# Placa_Final_Embebidos_Displays.net
KiCad netlist of a schematic drawn in Altium Designer
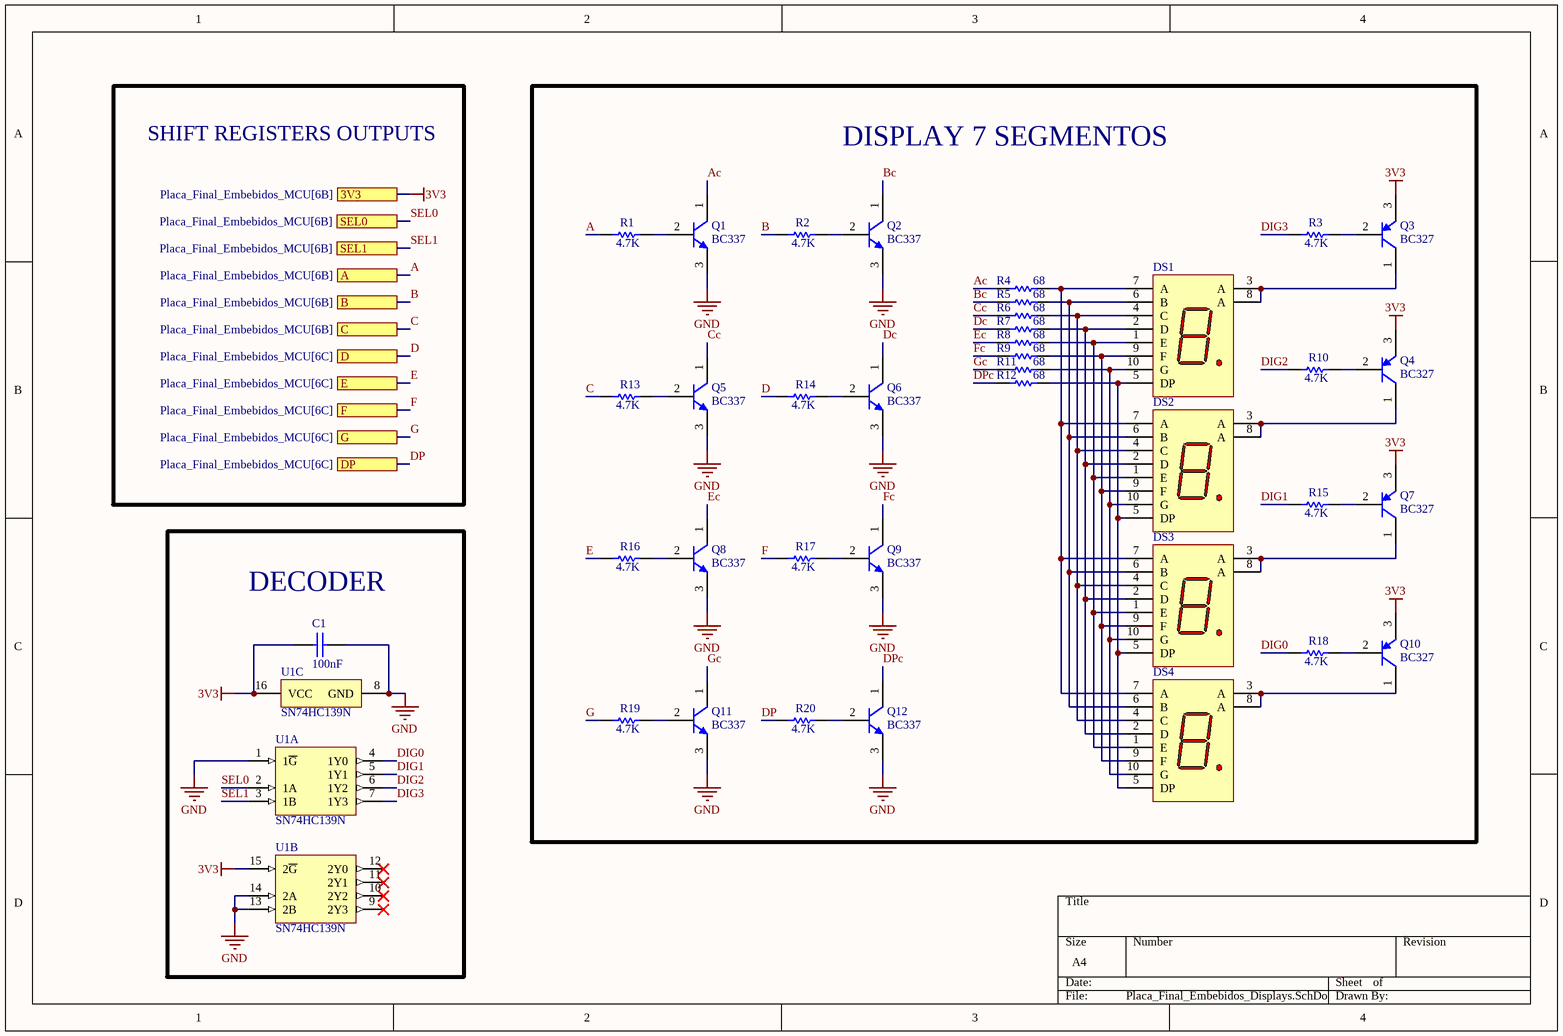
[diagram p0: Placa_Final_Embebidos_Displays.SchDoc]

(export (version "E")
  (design (tool "Eeschema 10.0.6"))
  (components
    (comp (ref "C1") (value "100nF") (footprint "CAP200") (libsource (lib "LIB PIO IX") (part "CAP")))
    (comp (ref "DS1")
      (value "~")
      (footprint "WL-T7DS_L17.5W12.4H7")
      (description "7-Seg Display, Comm Anode, Super Red Rohs Compliant: Yes")
      (libsource (lib "Altium Content Vault") (part "7 Segments_Red_CA_type 1"))
    )
    (comp (ref "DS2")
      (value "~")
      (footprint "WL-T7DS_L17.5W12.4H7")
      (description "7-Seg Display, Comm Anode, Super Red Rohs Compliant: Yes")
      (libsource (lib "Altium Content Vault") (part "7 Segments_Red_CA_type 1"))
    )
    (comp (ref "DS3")
      (value "~")
      (footprint "WL-T7DS_L17.5W12.4H7")
      (description "7-Seg Display, Comm Anode, Super Red Rohs Compliant: Yes")
      (libsource (lib "Altium Content Vault") (part "7 Segments_Red_CA_type 1"))
    )
    (comp (ref "DS4")
      (value "~")
      (footprint "WL-T7DS_L17.5W12.4H7")
      (description "7-Seg Display, Comm Anode, Super Red Rohs Compliant: Yes")
      (libsource (lib "Altium Content Vault") (part "7 Segments_Red_CA_type 1"))
    )
    (comp (ref "Q1")
      (value "BC337")
      (footprint "ONSC-TO-92-3-29-11_AM_BL")
      (description "Amplifier Transistor, NPN Silicon, 3-Pin TO-92, Pb-Free, Ammo Box")
      (fields (field (name "PARTNUMBER") "BC337-40ZL1G") (field (name "MANUFACTURER") "On Semiconductor"))
      (libsource (lib "Altium Content Vault") (part "ONSC-NPN-C1B2E3-3"))
    )
    (comp (ref "Q2")
      (value "BC337")
      (footprint "ONSC-TO-92-3-29-11_AM_BL")
      (description "Amplifier Transistor, NPN Silicon, 3-Pin TO-92, Pb-Free, Ammo Box")
      (fields (field (name "PARTNUMBER") "BC337-40ZL1G") (field (name "MANUFACTURER") "On Semiconductor"))
      (libsource (lib "Altium Content Vault") (part "ONSC-NPN-C1B2E3-3"))
    )
    (comp (ref "Q3")
      (value "BC327")
      (footprint "ONSC-TO-92-3-29-11_AM_BL")
      (description "Amplifier Transistor, PNP Silicon, 3-Pin TO-92, Pb-Free, Ammo Box")
      (fields (field (name "MANUFACTURER") "On Semiconductor") (field (name "PARTNUMBER") "BC327-25ZL1G"))
      (libsource (lib "Altium Content Vault") (part "ONSC-PNP-C1B2E3-3"))
    )
    (comp (ref "Q4")
      (value "BC327")
      (footprint "ONSC-TO-92-3-29-11_AM_BL")
      (description "Amplifier Transistor, PNP Silicon, 3-Pin TO-92, Pb-Free, Ammo Box")
      (fields (field (name "MANUFACTURER") "On Semiconductor") (field (name "PARTNUMBER") "BC327-25ZL1G"))
      (libsource (lib "Altium Content Vault") (part "ONSC-PNP-C1B2E3-3"))
    )
    (comp (ref "Q5")
      (value "BC337")
      (footprint "ONSC-TO-92-3-29-11_AM_BL")
      (description "Amplifier Transistor, NPN Silicon, 3-Pin TO-92, Pb-Free, Ammo Box")
      (fields (field (name "PARTNUMBER") "BC337-40ZL1G") (field (name "MANUFACTURER") "On Semiconductor"))
      (libsource (lib "Altium Content Vault") (part "ONSC-NPN-C1B2E3-3"))
    )
    (comp (ref "Q6")
      (value "BC337")
      (footprint "ONSC-TO-92-3-29-11_AM_BL")
      (description "Amplifier Transistor, NPN Silicon, 3-Pin TO-92, Pb-Free, Ammo Box")
      (fields (field (name "PARTNUMBER") "BC337-40ZL1G") (field (name "MANUFACTURER") "On Semiconductor"))
      (libsource (lib "Altium Content Vault") (part "ONSC-NPN-C1B2E3-3"))
    )
    (comp (ref "Q7")
      (value "BC327")
      (footprint "ONSC-TO-92-3-29-11_AM_BL")
      (description "Amplifier Transistor, PNP Silicon, 3-Pin TO-92, Pb-Free, Ammo Box")
      (fields (field (name "MANUFACTURER") "On Semiconductor") (field (name "PARTNUMBER") "BC327-25ZL1G"))
      (libsource (lib "Altium Content Vault") (part "ONSC-PNP-C1B2E3-3"))
    )
    (comp (ref "Q8")
      (value "BC337")
      (footprint "ONSC-TO-92-3-29-11_AM_BL")
      (description "Amplifier Transistor, NPN Silicon, 3-Pin TO-92, Pb-Free, Ammo Box")
      (fields (field (name "PARTNUMBER") "BC337-40ZL1G") (field (name "MANUFACTURER") "On Semiconductor"))
      (libsource (lib "Altium Content Vault") (part "ONSC-NPN-C1B2E3-3"))
    )
    (comp (ref "Q9")
      (value "BC337")
      (footprint "ONSC-TO-92-3-29-11_AM_BL")
      (description "Amplifier Transistor, NPN Silicon, 3-Pin TO-92, Pb-Free, Ammo Box")
      (fields (field (name "PARTNUMBER") "BC337-40ZL1G") (field (name "MANUFACTURER") "On Semiconductor"))
      (libsource (lib "Altium Content Vault") (part "ONSC-NPN-C1B2E3-3"))
    )
    (comp (ref "Q10")
      (value "BC327")
      (footprint "ONSC-TO-92-3-29-11_AM_BL")
      (description "Amplifier Transistor, PNP Silicon, 3-Pin TO-92, Pb-Free, Ammo Box")
      (fields (field (name "MANUFACTURER") "On Semiconductor") (field (name "PARTNUMBER") "BC327-25ZL1G"))
      (libsource (lib "Altium Content Vault") (part "ONSC-PNP-C1B2E3-3"))
    )
    (comp (ref "Q11")
      (value "BC337")
      (footprint "ONSC-TO-92-3-29-11_AM_BL")
      (description "Amplifier Transistor, NPN Silicon, 3-Pin TO-92, Pb-Free, Ammo Box")
      (fields (field (name "PARTNUMBER") "BC337-40ZL1G") (field (name "MANUFACTURER") "On Semiconductor"))
      (libsource (lib "Altium Content Vault") (part "ONSC-NPN-C1B2E3-3"))
    )
    (comp (ref "Q12")
      (value "BC337")
      (footprint "ONSC-TO-92-3-29-11_AM_BL")
      (description "Amplifier Transistor, NPN Silicon, 3-Pin TO-92, Pb-Free, Ammo Box")
      (fields (field (name "PARTNUMBER") "BC337-40ZL1G") (field (name "MANUFACTURER") "On Semiconductor"))
      (libsource (lib "Altium Content Vault") (part "ONSC-NPN-C1B2E3-3"))
    )
    (comp (ref "R1") (value "4.7K") (footprint "RES400") (libsource (lib "LIB PIO IX") (part "RES")))
    (comp (ref "R2") (value "4.7K") (footprint "RES400") (libsource (lib "LIB PIO IX") (part "RES")))
    (comp (ref "R3") (value "4.7K") (footprint "RES400") (libsource (lib "LIB PIO IX") (part "RES")))
    (comp (ref "R4") (value "68") (footprint "RES400") (libsource (lib "LIB PIO IX") (part "RES")))
    (comp (ref "R5") (value "68") (footprint "RES400") (libsource (lib "LIB PIO IX") (part "RES")))
    (comp (ref "R6") (value "68") (footprint "RES400") (libsource (lib "LIB PIO IX") (part "RES")))
    (comp (ref "R7") (value "68") (footprint "RES400") (libsource (lib "LIB PIO IX") (part "RES")))
    (comp (ref "R8") (value "68") (footprint "RES400") (libsource (lib "LIB PIO IX") (part "RES")))
    (comp (ref "R9") (value "68") (footprint "RES400") (libsource (lib "LIB PIO IX") (part "RES")))
    (comp (ref "R10") (value "4.7K") (footprint "RES400") (libsource (lib "LIB PIO IX") (part "RES")))
    (comp (ref "R11") (value "68") (footprint "RES400") (libsource (lib "LIB PIO IX") (part "RES")))
    (comp (ref "R12") (value "68") (footprint "RES400") (libsource (lib "LIB PIO IX") (part "RES")))
    (comp (ref "R13") (value "4.7K") (footprint "RES400") (libsource (lib "LIB PIO IX") (part "RES")))
    (comp (ref "R14") (value "4.7K") (footprint "RES400") (libsource (lib "LIB PIO IX") (part "RES")))
    (comp (ref "R15") (value "4.7K") (footprint "RES400") (libsource (lib "LIB PIO IX") (part "RES")))
    (comp (ref "R16") (value "4.7K") (footprint "RES400") (libsource (lib "LIB PIO IX") (part "RES")))
    (comp (ref "R17") (value "4.7K") (footprint "RES400") (libsource (lib "LIB PIO IX") (part "RES")))
    (comp (ref "R18") (value "4.7K") (footprint "RES400") (libsource (lib "LIB PIO IX") (part "RES")))
    (comp (ref "R19") (value "4.7K") (footprint "RES400") (libsource (lib "LIB PIO IX") (part "RES")))
    (comp (ref "R20") (value "4.7K") (footprint "RES400") (libsource (lib "LIB PIO IX") (part "RES")))
    (comp (ref "U1")
      (value "SN74HC139N")
      (footprint "N0016A")
      (description "Dual 2-Line To 4-Line Decoders/Demultiplexers, N0016A, TUBE")
      (fields
        (field (name "GENERIC PART NUMBER") "SN74HC139")
        (field (name "MANUFACTURER") "Texas Instruments")
      )
      (libsource (lib "Altium Content Vault") (part "TI-CD_SNX4XXX139-16"))
    )
  )
  (nets
    (net (code "1") (name "/A") (class "Default")
      (node (ref "R1") (pin "1") (pinfunction "1_1") (pintype "passive"))
    )
    (net (code "2") (name "/Ac") (class "Default")
      (node (ref "Q1") (pin "1") (pinfunction "C_1") (pintype "passive"))
      (node (ref "R4") (pin "1") (pinfunction "1_1") (pintype "passive"))
    )
    (net (code "3") (name "/B") (class "Default")
      (node (ref "R2") (pin "1") (pinfunction "1_1") (pintype "passive"))
    )
    (net (code "4") (name "/Bc") (class "Default")
      (node (ref "Q2") (pin "1") (pinfunction "C_1") (pintype "passive"))
      (node (ref "R5") (pin "1") (pinfunction "1_1") (pintype "passive"))
    )
    (net (code "5") (name "/C") (class "Default")
      (node (ref "R13") (pin "1") (pinfunction "1_1") (pintype "passive"))
    )
    (net (code "6") (name "/Cc") (class "Default")
      (node (ref "Q5") (pin "1") (pinfunction "C_1") (pintype "passive"))
      (node (ref "R6") (pin "1") (pinfunction "1_1") (pintype "passive"))
    )
    (net (code "7") (name "/D") (class "Default")
      (node (ref "R14") (pin "1") (pinfunction "1_1") (pintype "passive"))
    )
    (net (code "8") (name "/DIG0") (class "Default")
      (node (ref "R18") (pin "1") (pinfunction "1_1") (pintype "passive"))
      (node (ref "U1") (pin "4") (pinfunction "1Y0_4") (pintype "output"))
    )
    (net (code "9") (name "/DIG1") (class "Default")
      (node (ref "R15") (pin "1") (pinfunction "1_1") (pintype "passive"))
      (node (ref "U1") (pin "5") (pinfunction "1Y1_5") (pintype "output"))
    )
    (net (code "10") (name "/DIG2") (class "Default")
      (node (ref "R10") (pin "1") (pinfunction "1_1") (pintype "passive"))
      (node (ref "U1") (pin "6") (pinfunction "1Y2_6") (pintype "output"))
    )
    (net (code "11") (name "/DIG3") (class "Default")
      (node (ref "R3") (pin "1") (pinfunction "1_1") (pintype "passive"))
      (node (ref "U1") (pin "7") (pinfunction "1Y3_7") (pintype "output"))
    )
    (net (code "12") (name "/DP") (class "Default")
      (node (ref "R20") (pin "1") (pinfunction "1_1") (pintype "passive"))
    )
    (net (code "13") (name "/DPc") (class "Default")
      (node (ref "Q12") (pin "1") (pinfunction "C_1") (pintype "passive"))
      (node (ref "R12") (pin "1") (pinfunction "1_1") (pintype "passive"))
    )
    (net (code "14") (name "/Dc") (class "Default")
      (node (ref "Q6") (pin "1") (pinfunction "C_1") (pintype "passive"))
      (node (ref "R7") (pin "1") (pinfunction "1_1") (pintype "passive"))
    )
    (net (code "15") (name "/E") (class "Default")
      (node (ref "R16") (pin "1") (pinfunction "1_1") (pintype "passive"))
    )
    (net (code "16") (name "/Ec") (class "Default")
      (node (ref "Q8") (pin "1") (pinfunction "C_1") (pintype "passive"))
      (node (ref "R8") (pin "1") (pinfunction "1_1") (pintype "passive"))
    )
    (net (code "17") (name "/F") (class "Default")
      (node (ref "R17") (pin "1") (pinfunction "1_1") (pintype "passive"))
    )
    (net (code "18") (name "/Fc") (class "Default")
      (node (ref "Q9") (pin "1") (pinfunction "C_1") (pintype "passive"))
      (node (ref "R9") (pin "1") (pinfunction "1_1") (pintype "passive"))
    )
    (net (code "19") (name "/G") (class "Default")
      (node (ref "R19") (pin "1") (pinfunction "1_1") (pintype "passive"))
    )
    (net (code "20") (name "/Gc") (class "Default")
      (node (ref "Q11") (pin "1") (pinfunction "C_1") (pintype "passive"))
      (node (ref "R11") (pin "1") (pinfunction "1_1") (pintype "passive"))
    )
    (net (code "21") (name "/SEL0") (class "Default")
      (node (ref "U1") (pin "2") (pinfunction "1A_2") (pintype "input"))
    )
    (net (code "22") (name "/SEL1") (class "Default")
      (node (ref "U1") (pin "3") (pinfunction "1B_3") (pintype "input"))
    )
    (net (code "23") (name "3V3") (class "Default")
      (node (ref "C1") (pin "1") (pinfunction "1_1") (pintype "passive"))
      (node (ref "Q10") (pin "3") (pinfunction "E_3") (pintype "passive"))
      (node (ref "Q3") (pin "3") (pinfunction "E_3") (pintype "passive"))
      (node (ref "Q4") (pin "3") (pinfunction "E_3") (pintype "passive"))
      (node (ref "Q7") (pin "3") (pinfunction "E_3") (pintype "passive"))
      (node (ref "U1") (pin "15") (pinfunction "2~{G}_15") (pintype "input"))
      (node (ref "U1") (pin "16") (pinfunction "VCC_16") (pintype "power_in"))
    )
    (net (code "24") (name "GND") (class "Default")
      (node (ref "C1") (pin "2") (pinfunction "2_2") (pintype "passive"))
      (node (ref "Q1") (pin "3") (pinfunction "E_3") (pintype "passive"))
      (node (ref "Q11") (pin "3") (pinfunction "E_3") (pintype "passive"))
      (node (ref "Q12") (pin "3") (pinfunction "E_3") (pintype "passive"))
      (node (ref "Q2") (pin "3") (pinfunction "E_3") (pintype "passive"))
      (node (ref "Q5") (pin "3") (pinfunction "E_3") (pintype "passive"))
      (node (ref "Q6") (pin "3") (pinfunction "E_3") (pintype "passive"))
      (node (ref "Q8") (pin "3") (pinfunction "E_3") (pintype "passive"))
      (node (ref "Q9") (pin "3") (pinfunction "E_3") (pintype "passive"))
      (node (ref "U1") (pin "1") (pinfunction "1~{G}_1") (pintype "input"))
      (node (ref "U1") (pin "13") (pinfunction "2B_13") (pintype "input"))
      (node (ref "U1") (pin "14") (pinfunction "2A_14") (pintype "input"))
      (node (ref "U1") (pin "8") (pinfunction "GND_8") (pintype "power_in"))
    )
    (net (code "25") (name "Net-(DS1-A-Pad7)") (class "Default")
      (node (ref "DS1") (pin "7") (pinfunction "A_7") (pintype "passive"))
      (node (ref "DS2") (pin "7") (pinfunction "A_7") (pintype "passive"))
      (node (ref "DS3") (pin "7") (pinfunction "A_7") (pintype "passive"))
      (node (ref "DS4") (pin "7") (pinfunction "A_7") (pintype "passive"))
      (node (ref "R4") (pin "2") (pinfunction "2_2") (pintype "passive"))
    )
    (net (code "26") (name "Net-(DS1-B)") (class "Default")
      (node (ref "DS1") (pin "6") (pinfunction "B_6") (pintype "passive"))
      (node (ref "DS2") (pin "6") (pinfunction "B_6") (pintype "passive"))
      (node (ref "DS3") (pin "6") (pinfunction "B_6") (pintype "passive"))
      (node (ref "DS4") (pin "6") (pinfunction "B_6") (pintype "passive"))
      (node (ref "R5") (pin "2") (pinfunction "2_2") (pintype "passive"))
    )
    (net (code "27") (name "Net-(DS1-C)") (class "Default")
      (node (ref "DS1") (pin "4") (pinfunction "C_4") (pintype "passive"))
      (node (ref "DS2") (pin "4") (pinfunction "C_4") (pintype "passive"))
      (node (ref "DS3") (pin "4") (pinfunction "C_4") (pintype "passive"))
      (node (ref "DS4") (pin "4") (pinfunction "C_4") (pintype "passive"))
      (node (ref "R6") (pin "2") (pinfunction "2_2") (pintype "passive"))
    )
    (net (code "28") (name "Net-(DS1-D)") (class "Default")
      (node (ref "DS1") (pin "2") (pinfunction "D_2") (pintype "passive"))
      (node (ref "DS2") (pin "2") (pinfunction "D_2") (pintype "passive"))
      (node (ref "DS3") (pin "2") (pinfunction "D_2") (pintype "passive"))
      (node (ref "DS4") (pin "2") (pinfunction "D_2") (pintype "passive"))
      (node (ref "R7") (pin "2") (pinfunction "2_2") (pintype "passive"))
    )
    (net (code "29") (name "Net-(DS1-DP)") (class "Default")
      (node (ref "DS1") (pin "5") (pinfunction "DP_5") (pintype "passive"))
      (node (ref "DS2") (pin "5") (pinfunction "DP_5") (pintype "passive"))
      (node (ref "DS3") (pin "5") (pinfunction "DP_5") (pintype "passive"))
      (node (ref "DS4") (pin "5") (pinfunction "DP_5") (pintype "passive"))
      (node (ref "R12") (pin "2") (pinfunction "2_2") (pintype "passive"))
    )
    (net (code "30") (name "Net-(DS1-E)") (class "Default")
      (node (ref "DS1") (pin "1") (pinfunction "E_1") (pintype "passive"))
      (node (ref "DS2") (pin "1") (pinfunction "E_1") (pintype "passive"))
      (node (ref "DS3") (pin "1") (pinfunction "E_1") (pintype "passive"))
      (node (ref "DS4") (pin "1") (pinfunction "E_1") (pintype "passive"))
      (node (ref "R8") (pin "2") (pinfunction "2_2") (pintype "passive"))
    )
    (net (code "31") (name "Net-(DS1-F)") (class "Default")
      (node (ref "DS1") (pin "9") (pinfunction "F_9") (pintype "passive"))
      (node (ref "DS2") (pin "9") (pinfunction "F_9") (pintype "passive"))
      (node (ref "DS3") (pin "9") (pinfunction "F_9") (pintype "passive"))
      (node (ref "DS4") (pin "9") (pinfunction "F_9") (pintype "passive"))
      (node (ref "R9") (pin "2") (pinfunction "2_2") (pintype "passive"))
    )
    (net (code "32") (name "Net-(DS1-G)") (class "Default")
      (node (ref "DS1") (pin "10") (pinfunction "G_10") (pintype "passive"))
      (node (ref "DS2") (pin "10") (pinfunction "G_10") (pintype "passive"))
      (node (ref "DS3") (pin "10") (pinfunction "G_10") (pintype "passive"))
      (node (ref "DS4") (pin "10") (pinfunction "G_10") (pintype "passive"))
      (node (ref "R11") (pin "2") (pinfunction "2_2") (pintype "passive"))
    )
    (net (code "33") (name "Net-(Q1-B)") (class "Default")
      (node (ref "Q1") (pin "2") (pinfunction "B_2") (pintype "passive"))
      (node (ref "R1") (pin "2") (pinfunction "2_2") (pintype "passive"))
    )
    (net (code "34") (name "Net-(Q2-B)") (class "Default")
      (node (ref "Q2") (pin "2") (pinfunction "B_2") (pintype "passive"))
      (node (ref "R2") (pin "2") (pinfunction "2_2") (pintype "passive"))
    )
    (net (code "35") (name "Net-(Q3-B)") (class "Default")
      (node (ref "Q3") (pin "2") (pinfunction "B_2") (pintype "passive"))
      (node (ref "R3") (pin "2") (pinfunction "2_2") (pintype "passive"))
    )
    (net (code "36") (name "Net-(Q3-C)") (class "Default")
      (node (ref "DS1") (pin "3") (pinfunction "A_3") (pintype "passive"))
      (node (ref "DS1") (pin "8") (pinfunction "A_8") (pintype "passive"))
      (node (ref "Q3") (pin "1") (pinfunction "C_1") (pintype "passive"))
    )
    (net (code "37") (name "Net-(Q4-B)") (class "Default")
      (node (ref "Q4") (pin "2") (pinfunction "B_2") (pintype "passive"))
      (node (ref "R10") (pin "2") (pinfunction "2_2") (pintype "passive"))
    )
    (net (code "38") (name "Net-(Q4-C)") (class "Default")
      (node (ref "DS2") (pin "3") (pinfunction "A_3") (pintype "passive"))
      (node (ref "DS2") (pin "8") (pinfunction "A_8") (pintype "passive"))
      (node (ref "Q4") (pin "1") (pinfunction "C_1") (pintype "passive"))
    )
    (net (code "39") (name "Net-(Q5-B)") (class "Default")
      (node (ref "Q5") (pin "2") (pinfunction "B_2") (pintype "passive"))
      (node (ref "R13") (pin "2") (pinfunction "2_2") (pintype "passive"))
    )
    (net (code "40") (name "Net-(Q6-B)") (class "Default")
      (node (ref "Q6") (pin "2") (pinfunction "B_2") (pintype "passive"))
      (node (ref "R14") (pin "2") (pinfunction "2_2") (pintype "passive"))
    )
    (net (code "41") (name "Net-(Q7-B)") (class "Default")
      (node (ref "Q7") (pin "2") (pinfunction "B_2") (pintype "passive"))
      (node (ref "R15") (pin "2") (pinfunction "2_2") (pintype "passive"))
    )
    (net (code "42") (name "Net-(Q7-C)") (class "Default")
      (node (ref "DS3") (pin "3") (pinfunction "A_3") (pintype "passive"))
      (node (ref "DS3") (pin "8") (pinfunction "A_8") (pintype "passive"))
      (node (ref "Q7") (pin "1") (pinfunction "C_1") (pintype "passive"))
    )
    (net (code "43") (name "Net-(Q8-B)") (class "Default")
      (node (ref "Q8") (pin "2") (pinfunction "B_2") (pintype "passive"))
      (node (ref "R16") (pin "2") (pinfunction "2_2") (pintype "passive"))
    )
    (net (code "44") (name "Net-(Q9-B)") (class "Default")
      (node (ref "Q9") (pin "2") (pinfunction "B_2") (pintype "passive"))
      (node (ref "R17") (pin "2") (pinfunction "2_2") (pintype "passive"))
    )
    (net (code "45") (name "Net-(Q10-B)") (class "Default")
      (node (ref "Q10") (pin "2") (pinfunction "B_2") (pintype "passive"))
      (node (ref "R18") (pin "2") (pinfunction "2_2") (pintype "passive"))
    )
    (net (code "46") (name "Net-(Q10-C)") (class "Default")
      (node (ref "DS4") (pin "3") (pinfunction "A_3") (pintype "passive"))
      (node (ref "DS4") (pin "8") (pinfunction "A_8") (pintype "passive"))
      (node (ref "Q10") (pin "1") (pinfunction "C_1") (pintype "passive"))
    )
    (net (code "47") (name "Net-(Q11-B)") (class "Default")
      (node (ref "Q11") (pin "2") (pinfunction "B_2") (pintype "passive"))
      (node (ref "R19") (pin "2") (pinfunction "2_2") (pintype "passive"))
    )
    (net (code "48") (name "Net-(Q12-B)") (class "Default")
      (node (ref "Q12") (pin "2") (pinfunction "B_2") (pintype "passive"))
      (node (ref "R20") (pin "2") (pinfunction "2_2") (pintype "passive"))
    )
    (net (code "49") (name "unconnected-(U1B-2Y0-Pad12)") (class "Default")
      (node (ref "U1") (pin "12") (pinfunction "2Y0_12") (pintype "output+no_connect"))
    )
    (net (code "50") (name "unconnected-(U1B-2Y1-Pad11)") (class "Default")
      (node (ref "U1") (pin "11") (pinfunction "2Y1_11") (pintype "output+no_connect"))
    )
    (net (code "51") (name "unconnected-(U1B-2Y2-Pad10)") (class "Default")
      (node (ref "U1") (pin "10") (pinfunction "2Y2_10") (pintype "output+no_connect"))
    )
    (net (code "52") (name "unconnected-(U1B-2Y3-Pad9)") (class "Default")
      (node (ref "U1") (pin "9") (pinfunction "2Y3_9") (pintype "output+no_connect"))
    )
  )
)
